# Cube-Panel.net
KiCad netlist of a schematic drawn in EAGLE
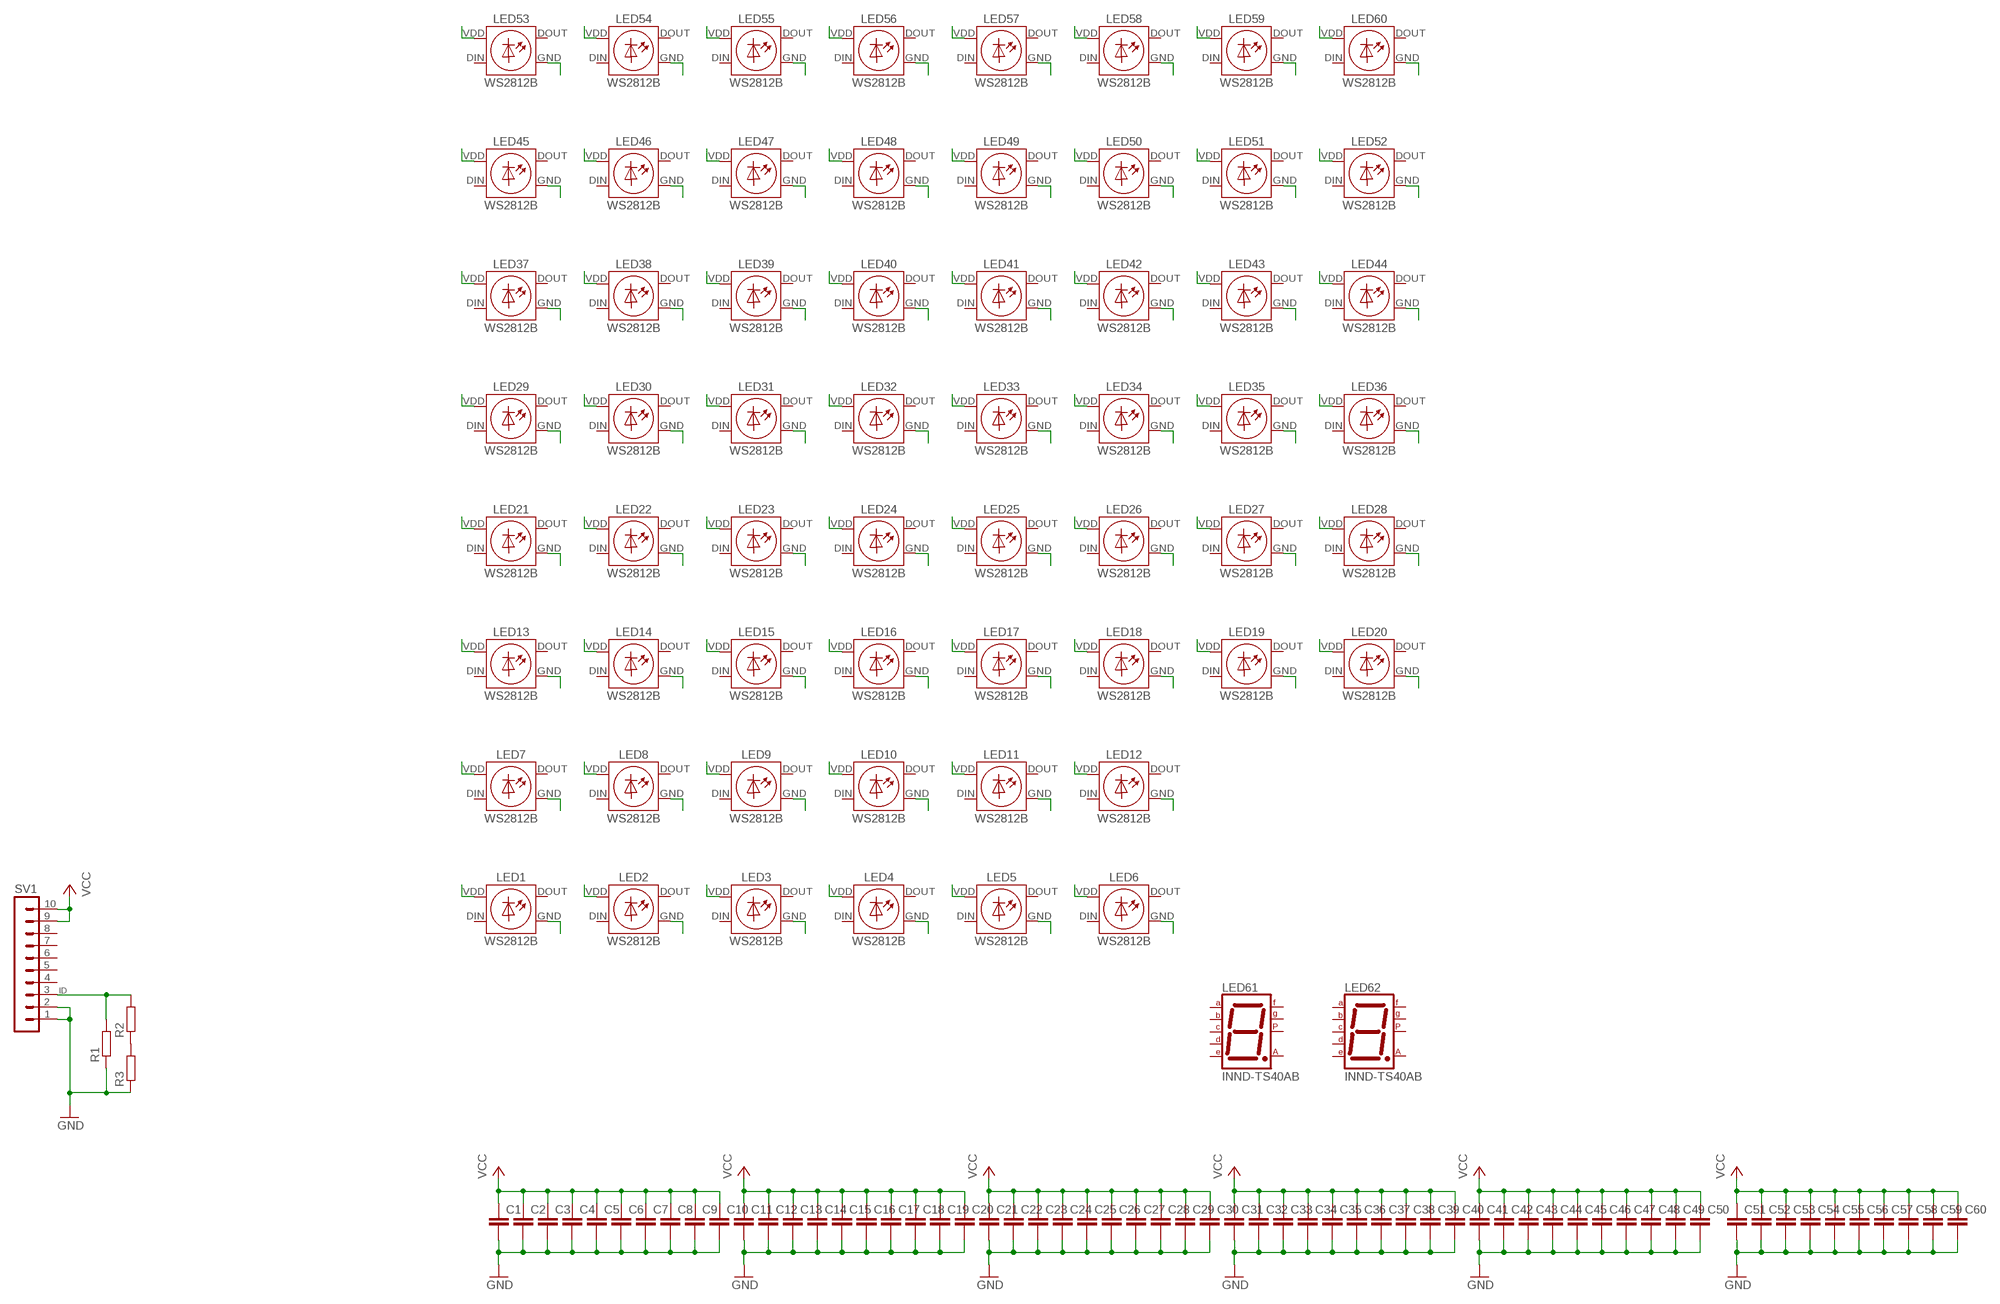
[diagram p0: schematic, sheet 1]

(export (version "E")
  (design (tool "Eeschema 10.0.6"))
  (components
    (comp (ref "C1")
      (value "KONDENSATOR-0603")
      (footprint "eagle-import:0603")
      (libsource (lib "eagle-import") (part "KONDENSATOR-0603"))
    )
    (comp (ref "C2")
      (value "KONDENSATOR-0603")
      (footprint "eagle-import:0603")
      (libsource (lib "eagle-import") (part "KONDENSATOR-0603"))
    )
    (comp (ref "C3")
      (value "KONDENSATOR-0603")
      (footprint "eagle-import:0603")
      (libsource (lib "eagle-import") (part "KONDENSATOR-0603"))
    )
    (comp (ref "C4")
      (value "KONDENSATOR-0603")
      (footprint "eagle-import:0603")
      (libsource (lib "eagle-import") (part "KONDENSATOR-0603"))
    )
    (comp (ref "C5")
      (value "KONDENSATOR-0603")
      (footprint "eagle-import:0603")
      (libsource (lib "eagle-import") (part "KONDENSATOR-0603"))
    )
    (comp (ref "C6")
      (value "KONDENSATOR-0603")
      (footprint "eagle-import:0603")
      (libsource (lib "eagle-import") (part "KONDENSATOR-0603"))
    )
    (comp (ref "C7")
      (value "KONDENSATOR-0603")
      (footprint "eagle-import:0603")
      (libsource (lib "eagle-import") (part "KONDENSATOR-0603"))
    )
    (comp (ref "C8")
      (value "KONDENSATOR-0603")
      (footprint "eagle-import:0603")
      (libsource (lib "eagle-import") (part "KONDENSATOR-0603"))
    )
    (comp (ref "C9")
      (value "KONDENSATOR-0603")
      (footprint "eagle-import:0603")
      (libsource (lib "eagle-import") (part "KONDENSATOR-0603"))
    )
    (comp (ref "C10")
      (value "KONDENSATOR-0603")
      (footprint "eagle-import:0603")
      (libsource (lib "eagle-import") (part "KONDENSATOR-0603"))
    )
    (comp (ref "C11")
      (value "KONDENSATOR-0603")
      (footprint "eagle-import:0603")
      (libsource (lib "eagle-import") (part "KONDENSATOR-0603"))
    )
    (comp (ref "C12")
      (value "KONDENSATOR-0603")
      (footprint "eagle-import:0603")
      (libsource (lib "eagle-import") (part "KONDENSATOR-0603"))
    )
    (comp (ref "C13")
      (value "KONDENSATOR-0603")
      (footprint "eagle-import:0603")
      (libsource (lib "eagle-import") (part "KONDENSATOR-0603"))
    )
    (comp (ref "C14")
      (value "KONDENSATOR-0603")
      (footprint "eagle-import:0603")
      (libsource (lib "eagle-import") (part "KONDENSATOR-0603"))
    )
    (comp (ref "C15")
      (value "KONDENSATOR-0603")
      (footprint "eagle-import:0603")
      (libsource (lib "eagle-import") (part "KONDENSATOR-0603"))
    )
    (comp (ref "C16")
      (value "KONDENSATOR-0603")
      (footprint "eagle-import:0603")
      (libsource (lib "eagle-import") (part "KONDENSATOR-0603"))
    )
    (comp (ref "C17")
      (value "KONDENSATOR-0603")
      (footprint "eagle-import:0603")
      (libsource (lib "eagle-import") (part "KONDENSATOR-0603"))
    )
    (comp (ref "C18")
      (value "KONDENSATOR-0603")
      (footprint "eagle-import:0603")
      (libsource (lib "eagle-import") (part "KONDENSATOR-0603"))
    )
    (comp (ref "C19")
      (value "KONDENSATOR-0603")
      (footprint "eagle-import:0603")
      (libsource (lib "eagle-import") (part "KONDENSATOR-0603"))
    )
    (comp (ref "C20")
      (value "KONDENSATOR-0603")
      (footprint "eagle-import:0603")
      (libsource (lib "eagle-import") (part "KONDENSATOR-0603"))
    )
    (comp (ref "C21")
      (value "KONDENSATOR-0603")
      (footprint "eagle-import:0603")
      (libsource (lib "eagle-import") (part "KONDENSATOR-0603"))
    )
    (comp (ref "C22")
      (value "KONDENSATOR-0603")
      (footprint "eagle-import:0603")
      (libsource (lib "eagle-import") (part "KONDENSATOR-0603"))
    )
    (comp (ref "C23")
      (value "KONDENSATOR-0603")
      (footprint "eagle-import:0603")
      (libsource (lib "eagle-import") (part "KONDENSATOR-0603"))
    )
    (comp (ref "C24")
      (value "KONDENSATOR-0603")
      (footprint "eagle-import:0603")
      (libsource (lib "eagle-import") (part "KONDENSATOR-0603"))
    )
    (comp (ref "C25")
      (value "KONDENSATOR-0603")
      (footprint "eagle-import:0603")
      (libsource (lib "eagle-import") (part "KONDENSATOR-0603"))
    )
    (comp (ref "C26")
      (value "KONDENSATOR-0603")
      (footprint "eagle-import:0603")
      (libsource (lib "eagle-import") (part "KONDENSATOR-0603"))
    )
    (comp (ref "C27")
      (value "KONDENSATOR-0603")
      (footprint "eagle-import:0603")
      (libsource (lib "eagle-import") (part "KONDENSATOR-0603"))
    )
    (comp (ref "C28")
      (value "KONDENSATOR-0603")
      (footprint "eagle-import:0603")
      (libsource (lib "eagle-import") (part "KONDENSATOR-0603"))
    )
    (comp (ref "C29")
      (value "KONDENSATOR-0603")
      (footprint "eagle-import:0603")
      (libsource (lib "eagle-import") (part "KONDENSATOR-0603"))
    )
    (comp (ref "C30")
      (value "KONDENSATOR-0603")
      (footprint "eagle-import:0603")
      (libsource (lib "eagle-import") (part "KONDENSATOR-0603"))
    )
    (comp (ref "C31")
      (value "KONDENSATOR-0603")
      (footprint "eagle-import:0603")
      (libsource (lib "eagle-import") (part "KONDENSATOR-0603"))
    )
    (comp (ref "C32")
      (value "KONDENSATOR-0603")
      (footprint "eagle-import:0603")
      (libsource (lib "eagle-import") (part "KONDENSATOR-0603"))
    )
    (comp (ref "C33")
      (value "KONDENSATOR-0603")
      (footprint "eagle-import:0603")
      (libsource (lib "eagle-import") (part "KONDENSATOR-0603"))
    )
    (comp (ref "C34")
      (value "KONDENSATOR-0603")
      (footprint "eagle-import:0603")
      (libsource (lib "eagle-import") (part "KONDENSATOR-0603"))
    )
    (comp (ref "C35")
      (value "KONDENSATOR-0603")
      (footprint "eagle-import:0603")
      (libsource (lib "eagle-import") (part "KONDENSATOR-0603"))
    )
    (comp (ref "C36")
      (value "KONDENSATOR-0603")
      (footprint "eagle-import:0603")
      (libsource (lib "eagle-import") (part "KONDENSATOR-0603"))
    )
    (comp (ref "C37")
      (value "KONDENSATOR-0603")
      (footprint "eagle-import:0603")
      (libsource (lib "eagle-import") (part "KONDENSATOR-0603"))
    )
    (comp (ref "C38")
      (value "KONDENSATOR-0603")
      (footprint "eagle-import:0603")
      (libsource (lib "eagle-import") (part "KONDENSATOR-0603"))
    )
    (comp (ref "C39")
      (value "KONDENSATOR-0603")
      (footprint "eagle-import:0603")
      (libsource (lib "eagle-import") (part "KONDENSATOR-0603"))
    )
    (comp (ref "C40")
      (value "KONDENSATOR-0603")
      (footprint "eagle-import:0603")
      (libsource (lib "eagle-import") (part "KONDENSATOR-0603"))
    )
    (comp (ref "C41")
      (value "KONDENSATOR-0603")
      (footprint "eagle-import:0603")
      (libsource (lib "eagle-import") (part "KONDENSATOR-0603"))
    )
    (comp (ref "C42")
      (value "KONDENSATOR-0603")
      (footprint "eagle-import:0603")
      (libsource (lib "eagle-import") (part "KONDENSATOR-0603"))
    )
    (comp (ref "C43")
      (value "KONDENSATOR-0603")
      (footprint "eagle-import:0603")
      (libsource (lib "eagle-import") (part "KONDENSATOR-0603"))
    )
    (comp (ref "C44")
      (value "KONDENSATOR-0603")
      (footprint "eagle-import:0603")
      (libsource (lib "eagle-import") (part "KONDENSATOR-0603"))
    )
    (comp (ref "C45")
      (value "KONDENSATOR-0603")
      (footprint "eagle-import:0603")
      (libsource (lib "eagle-import") (part "KONDENSATOR-0603"))
    )
    (comp (ref "C46")
      (value "KONDENSATOR-0603")
      (footprint "eagle-import:0603")
      (libsource (lib "eagle-import") (part "KONDENSATOR-0603"))
    )
    (comp (ref "C47")
      (value "KONDENSATOR-0603")
      (footprint "eagle-import:0603")
      (libsource (lib "eagle-import") (part "KONDENSATOR-0603"))
    )
    (comp (ref "C48")
      (value "KONDENSATOR-0603")
      (footprint "eagle-import:0603")
      (libsource (lib "eagle-import") (part "KONDENSATOR-0603"))
    )
    (comp (ref "C49")
      (value "KONDENSATOR-0603")
      (footprint "eagle-import:0603")
      (libsource (lib "eagle-import") (part "KONDENSATOR-0603"))
    )
    (comp (ref "C50")
      (value "KONDENSATOR-0603")
      (footprint "eagle-import:0603")
      (libsource (lib "eagle-import") (part "KONDENSATOR-0603"))
    )
    (comp (ref "C51")
      (value "KONDENSATOR-0603")
      (footprint "eagle-import:0603")
      (libsource (lib "eagle-import") (part "KONDENSATOR-0603"))
    )
    (comp (ref "C52")
      (value "KONDENSATOR-0603")
      (footprint "eagle-import:0603")
      (libsource (lib "eagle-import") (part "KONDENSATOR-0603"))
    )
    (comp (ref "C53")
      (value "KONDENSATOR-0603")
      (footprint "eagle-import:0603")
      (libsource (lib "eagle-import") (part "KONDENSATOR-0603"))
    )
    (comp (ref "C54")
      (value "KONDENSATOR-0603")
      (footprint "eagle-import:0603")
      (libsource (lib "eagle-import") (part "KONDENSATOR-0603"))
    )
    (comp (ref "C55")
      (value "KONDENSATOR-0603")
      (footprint "eagle-import:0603")
      (libsource (lib "eagle-import") (part "KONDENSATOR-0603"))
    )
    (comp (ref "C56")
      (value "KONDENSATOR-0603")
      (footprint "eagle-import:0603")
      (libsource (lib "eagle-import") (part "KONDENSATOR-0603"))
    )
    (comp (ref "C57")
      (value "KONDENSATOR-0603")
      (footprint "eagle-import:0603")
      (libsource (lib "eagle-import") (part "KONDENSATOR-0603"))
    )
    (comp (ref "C58")
      (value "KONDENSATOR-0603")
      (footprint "eagle-import:0603")
      (libsource (lib "eagle-import") (part "KONDENSATOR-0603"))
    )
    (comp (ref "C59")
      (value "KONDENSATOR-0603")
      (footprint "eagle-import:0603")
      (libsource (lib "eagle-import") (part "KONDENSATOR-0603"))
    )
    (comp (ref "C60")
      (value "KONDENSATOR-0603")
      (footprint "eagle-import:0603")
      (libsource (lib "eagle-import") (part "KONDENSATOR-0603"))
    )
    (comp (ref "LED1")
      (value "WS2812B")
      (footprint "eagle-import:WS2812B")
      (libsource (lib "eagle-import") (part "WS2812B"))
    )
    (comp (ref "LED2")
      (value "WS2812B")
      (footprint "eagle-import:WS2812B")
      (libsource (lib "eagle-import") (part "WS2812B"))
    )
    (comp (ref "LED3")
      (value "WS2812B")
      (footprint "eagle-import:WS2812B")
      (libsource (lib "eagle-import") (part "WS2812B"))
    )
    (comp (ref "LED4")
      (value "WS2812B")
      (footprint "eagle-import:WS2812B")
      (libsource (lib "eagle-import") (part "WS2812B"))
    )
    (comp (ref "LED5")
      (value "WS2812B")
      (footprint "eagle-import:WS2812B")
      (libsource (lib "eagle-import") (part "WS2812B"))
    )
    (comp (ref "LED6")
      (value "WS2812B")
      (footprint "eagle-import:WS2812B")
      (libsource (lib "eagle-import") (part "WS2812B"))
    )
    (comp (ref "LED7")
      (value "WS2812B")
      (footprint "eagle-import:WS2812B")
      (libsource (lib "eagle-import") (part "WS2812B"))
    )
    (comp (ref "LED8")
      (value "WS2812B")
      (footprint "eagle-import:WS2812B")
      (libsource (lib "eagle-import") (part "WS2812B"))
    )
    (comp (ref "LED9")
      (value "WS2812B")
      (footprint "eagle-import:WS2812B")
      (libsource (lib "eagle-import") (part "WS2812B"))
    )
    (comp (ref "LED10")
      (value "WS2812B")
      (footprint "eagle-import:WS2812B")
      (libsource (lib "eagle-import") (part "WS2812B"))
    )
    (comp (ref "LED11")
      (value "WS2812B")
      (footprint "eagle-import:WS2812B")
      (libsource (lib "eagle-import") (part "WS2812B"))
    )
    (comp (ref "LED12")
      (value "WS2812B")
      (footprint "eagle-import:WS2812B")
      (libsource (lib "eagle-import") (part "WS2812B"))
    )
    (comp (ref "LED13")
      (value "WS2812B")
      (footprint "eagle-import:WS2812B")
      (libsource (lib "eagle-import") (part "WS2812B"))
    )
    (comp (ref "LED14")
      (value "WS2812B")
      (footprint "eagle-import:WS2812B")
      (libsource (lib "eagle-import") (part "WS2812B"))
    )
    (comp (ref "LED15")
      (value "WS2812B")
      (footprint "eagle-import:WS2812B")
      (libsource (lib "eagle-import") (part "WS2812B"))
    )
    (comp (ref "LED16")
      (value "WS2812B")
      (footprint "eagle-import:WS2812B")
      (libsource (lib "eagle-import") (part "WS2812B"))
    )
    (comp (ref "LED17")
      (value "WS2812B")
      (footprint "eagle-import:WS2812B")
      (libsource (lib "eagle-import") (part "WS2812B"))
    )
    (comp (ref "LED18")
      (value "WS2812B")
      (footprint "eagle-import:WS2812B")
      (libsource (lib "eagle-import") (part "WS2812B"))
    )
    (comp (ref "LED19")
      (value "WS2812B")
      (footprint "eagle-import:WS2812B")
      (libsource (lib "eagle-import") (part "WS2812B"))
    )
    (comp (ref "LED20")
      (value "WS2812B")
      (footprint "eagle-import:WS2812B")
      (libsource (lib "eagle-import") (part "WS2812B"))
    )
    (comp (ref "LED21")
      (value "WS2812B")
      (footprint "eagle-import:WS2812B")
      (libsource (lib "eagle-import") (part "WS2812B"))
    )
    (comp (ref "LED22")
      (value "WS2812B")
      (footprint "eagle-import:WS2812B")
      (libsource (lib "eagle-import") (part "WS2812B"))
    )
    (comp (ref "LED23")
      (value "WS2812B")
      (footprint "eagle-import:WS2812B")
      (libsource (lib "eagle-import") (part "WS2812B"))
    )
    (comp (ref "LED24")
      (value "WS2812B")
      (footprint "eagle-import:WS2812B")
      (libsource (lib "eagle-import") (part "WS2812B"))
    )
    (comp (ref "LED25")
      (value "WS2812B")
      (footprint "eagle-import:WS2812B")
      (libsource (lib "eagle-import") (part "WS2812B"))
    )
    (comp (ref "LED26")
      (value "WS2812B")
      (footprint "eagle-import:WS2812B")
      (libsource (lib "eagle-import") (part "WS2812B"))
    )
    (comp (ref "LED27")
      (value "WS2812B")
      (footprint "eagle-import:WS2812B")
      (libsource (lib "eagle-import") (part "WS2812B"))
    )
    (comp (ref "LED28")
      (value "WS2812B")
      (footprint "eagle-import:WS2812B")
      (libsource (lib "eagle-import") (part "WS2812B"))
    )
    (comp (ref "LED29")
      (value "WS2812B")
      (footprint "eagle-import:WS2812B")
      (libsource (lib "eagle-import") (part "WS2812B"))
    )
    (comp (ref "LED30")
      (value "WS2812B")
      (footprint "eagle-import:WS2812B")
      (libsource (lib "eagle-import") (part "WS2812B"))
    )
    (comp (ref "LED31")
      (value "WS2812B")
      (footprint "eagle-import:WS2812B")
      (libsource (lib "eagle-import") (part "WS2812B"))
    )
    (comp (ref "LED32")
      (value "WS2812B")
      (footprint "eagle-import:WS2812B")
      (libsource (lib "eagle-import") (part "WS2812B"))
    )
    (comp (ref "LED33")
      (value "WS2812B")
      (footprint "eagle-import:WS2812B")
      (libsource (lib "eagle-import") (part "WS2812B"))
    )
    (comp (ref "LED34")
      (value "WS2812B")
      (footprint "eagle-import:WS2812B")
      (libsource (lib "eagle-import") (part "WS2812B"))
    )
    (comp (ref "LED35")
      (value "WS2812B")
      (footprint "eagle-import:WS2812B")
      (libsource (lib "eagle-import") (part "WS2812B"))
    )
    (comp (ref "LED36")
      (value "WS2812B")
      (footprint "eagle-import:WS2812B")
      (libsource (lib "eagle-import") (part "WS2812B"))
    )
    (comp (ref "LED37")
      (value "WS2812B")
      (footprint "eagle-import:WS2812B")
      (libsource (lib "eagle-import") (part "WS2812B"))
    )
    (comp (ref "LED38")
      (value "WS2812B")
      (footprint "eagle-import:WS2812B")
      (libsource (lib "eagle-import") (part "WS2812B"))
    )
    (comp (ref "LED39")
      (value "WS2812B")
      (footprint "eagle-import:WS2812B")
      (libsource (lib "eagle-import") (part "WS2812B"))
    )
    (comp (ref "LED40")
      (value "WS2812B")
      (footprint "eagle-import:WS2812B")
      (libsource (lib "eagle-import") (part "WS2812B"))
    )
    (comp (ref "LED41")
      (value "WS2812B")
      (footprint "eagle-import:WS2812B")
      (libsource (lib "eagle-import") (part "WS2812B"))
    )
    (comp (ref "LED42")
      (value "WS2812B")
      (footprint "eagle-import:WS2812B")
      (libsource (lib "eagle-import") (part "WS2812B"))
    )
    (comp (ref "LED43")
      (value "WS2812B")
      (footprint "eagle-import:WS2812B")
      (libsource (lib "eagle-import") (part "WS2812B"))
    )
    (comp (ref "LED44")
      (value "WS2812B")
      (footprint "eagle-import:WS2812B")
      (libsource (lib "eagle-import") (part "WS2812B"))
    )
    (comp (ref "LED45")
      (value "WS2812B")
      (footprint "eagle-import:WS2812B")
      (libsource (lib "eagle-import") (part "WS2812B"))
    )
    (comp (ref "LED46")
      (value "WS2812B")
      (footprint "eagle-import:WS2812B")
      (libsource (lib "eagle-import") (part "WS2812B"))
    )
    (comp (ref "LED47")
      (value "WS2812B")
      (footprint "eagle-import:WS2812B")
      (libsource (lib "eagle-import") (part "WS2812B"))
    )
    (comp (ref "LED48")
      (value "WS2812B")
      (footprint "eagle-import:WS2812B")
      (libsource (lib "eagle-import") (part "WS2812B"))
    )
    (comp (ref "LED49")
      (value "WS2812B")
      (footprint "eagle-import:WS2812B")
      (libsource (lib "eagle-import") (part "WS2812B"))
    )
    (comp (ref "LED50")
      (value "WS2812B")
      (footprint "eagle-import:WS2812B")
      (libsource (lib "eagle-import") (part "WS2812B"))
    )
    (comp (ref "LED51")
      (value "WS2812B")
      (footprint "eagle-import:WS2812B")
      (libsource (lib "eagle-import") (part "WS2812B"))
    )
    (comp (ref "LED52")
      (value "WS2812B")
      (footprint "eagle-import:WS2812B")
      (libsource (lib "eagle-import") (part "WS2812B"))
    )
    (comp (ref "LED53")
      (value "WS2812B")
      (footprint "eagle-import:WS2812B")
      (libsource (lib "eagle-import") (part "WS2812B"))
    )
    (comp (ref "LED54")
      (value "WS2812B")
      (footprint "eagle-import:WS2812B")
      (libsource (lib "eagle-import") (part "WS2812B"))
    )
    (comp (ref "LED55")
      (value "WS2812B")
      (footprint "eagle-import:WS2812B")
      (libsource (lib "eagle-import") (part "WS2812B"))
    )
    (comp (ref "LED56")
      (value "WS2812B")
      (footprint "eagle-import:WS2812B")
      (libsource (lib "eagle-import") (part "WS2812B"))
    )
    (comp (ref "LED57")
      (value "WS2812B")
      (footprint "eagle-import:WS2812B")
      (libsource (lib "eagle-import") (part "WS2812B"))
    )
    (comp (ref "LED58")
      (value "WS2812B")
      (footprint "eagle-import:WS2812B")
      (libsource (lib "eagle-import") (part "WS2812B"))
    )
    (comp (ref "LED59")
      (value "WS2812B")
      (footprint "eagle-import:WS2812B")
      (libsource (lib "eagle-import") (part "WS2812B"))
    )
    (comp (ref "LED60")
      (value "WS2812B")
      (footprint "eagle-import:WS2812B")
      (libsource (lib "eagle-import") (part "WS2812B"))
    )
    (comp (ref "LED61")
      (value "INND-TS40AB")
      (footprint "eagle-import:7SEG-13")
      (libsource (lib "eagle-import") (part "INND-TS40AB"))
    )
    (comp (ref "LED62")
      (value "INND-TS40AB")
      (footprint "eagle-import:7SEG-13")
      (libsource (lib "eagle-import") (part "INND-TS40AB"))
    )
    (comp (ref "R1")
      (value "WIDERSTAND_0603")
      (footprint "eagle-import:R0603")
      (libsource (lib "eagle-import") (part "WIDERSTAND_0603"))
    )
    (comp (ref "R2")
      (value "WIDERSTAND_0603")
      (footprint "eagle-import:R0603")
      (libsource (lib "eagle-import") (part "WIDERSTAND_0603"))
    )
    (comp (ref "R3")
      (value "WIDERSTAND_0603")
      (footprint "eagle-import:R0603")
      (libsource (lib "eagle-import") (part "WIDERSTAND_0603"))
    )
    (comp (ref "SV1")
      (value "MA10-1")
      (footprint "eagle-import:MA10-1")
      (libsource (lib "eagle-import") (part "MA10-1"))
    )
  )
  (nets
    (net (code "1") (name "/ID") (class "Default")
      (node (ref "R1") (pin "2") (pinfunction "2_2") (pintype "passive"))
      (node (ref "R2") (pin "2") (pinfunction "2_2") (pintype "passive"))
      (node (ref "SV1") (pin "3") (pinfunction "3_3") (pintype "passive"))
    )
    (net (code "2") (name "GND") (class "Default")
      (node (ref "C1") (pin "P$2") (pinfunction "2_P$2") (pintype "passive"))
      (node (ref "C10") (pin "P$2") (pinfunction "2_P$2") (pintype "passive"))
      (node (ref "C11") (pin "P$2") (pinfunction "2_P$2") (pintype "passive"))
      (node (ref "C12") (pin "P$2") (pinfunction "2_P$2") (pintype "passive"))
      (node (ref "C13") (pin "P$2") (pinfunction "2_P$2") (pintype "passive"))
      (node (ref "C14") (pin "P$2") (pinfunction "2_P$2") (pintype "passive"))
      (node (ref "C15") (pin "P$2") (pinfunction "2_P$2") (pintype "passive"))
      (node (ref "C16") (pin "P$2") (pinfunction "2_P$2") (pintype "passive"))
      (node (ref "C17") (pin "P$2") (pinfunction "2_P$2") (pintype "passive"))
      (node (ref "C18") (pin "P$2") (pinfunction "2_P$2") (pintype "passive"))
      (node (ref "C19") (pin "P$2") (pinfunction "2_P$2") (pintype "passive"))
      (node (ref "C2") (pin "P$2") (pinfunction "2_P$2") (pintype "passive"))
      (node (ref "C20") (pin "P$2") (pinfunction "2_P$2") (pintype "passive"))
      (node (ref "C21") (pin "P$2") (pinfunction "2_P$2") (pintype "passive"))
      (node (ref "C22") (pin "P$2") (pinfunction "2_P$2") (pintype "passive"))
      (node (ref "C23") (pin "P$2") (pinfunction "2_P$2") (pintype "passive"))
      (node (ref "C24") (pin "P$2") (pinfunction "2_P$2") (pintype "passive"))
      (node (ref "C25") (pin "P$2") (pinfunction "2_P$2") (pintype "passive"))
      (node (ref "C26") (pin "P$2") (pinfunction "2_P$2") (pintype "passive"))
      (node (ref "C27") (pin "P$2") (pinfunction "2_P$2") (pintype "passive"))
      (node (ref "C28") (pin "P$2") (pinfunction "2_P$2") (pintype "passive"))
      (node (ref "C29") (pin "P$2") (pinfunction "2_P$2") (pintype "passive"))
      (node (ref "C3") (pin "P$2") (pinfunction "2_P$2") (pintype "passive"))
      (node (ref "C30") (pin "P$2") (pinfunction "2_P$2") (pintype "passive"))
      (node (ref "C31") (pin "P$2") (pinfunction "2_P$2") (pintype "passive"))
      (node (ref "C32") (pin "P$2") (pinfunction "2_P$2") (pintype "passive"))
      (node (ref "C33") (pin "P$2") (pinfunction "2_P$2") (pintype "passive"))
      (node (ref "C34") (pin "P$2") (pinfunction "2_P$2") (pintype "passive"))
      (node (ref "C35") (pin "P$2") (pinfunction "2_P$2") (pintype "passive"))
      (node (ref "C36") (pin "P$2") (pinfunction "2_P$2") (pintype "passive"))
      (node (ref "C37") (pin "P$2") (pinfunction "2_P$2") (pintype "passive"))
      (node (ref "C38") (pin "P$2") (pinfunction "2_P$2") (pintype "passive"))
      (node (ref "C39") (pin "P$2") (pinfunction "2_P$2") (pintype "passive"))
      (node (ref "C4") (pin "P$2") (pinfunction "2_P$2") (pintype "passive"))
      (node (ref "C40") (pin "P$2") (pinfunction "2_P$2") (pintype "passive"))
      (node (ref "C41") (pin "P$2") (pinfunction "2_P$2") (pintype "passive"))
      (node (ref "C42") (pin "P$2") (pinfunction "2_P$2") (pintype "passive"))
      (node (ref "C43") (pin "P$2") (pinfunction "2_P$2") (pintype "passive"))
      (node (ref "C44") (pin "P$2") (pinfunction "2_P$2") (pintype "passive"))
      (node (ref "C45") (pin "P$2") (pinfunction "2_P$2") (pintype "passive"))
      (node (ref "C46") (pin "P$2") (pinfunction "2_P$2") (pintype "passive"))
      (node (ref "C47") (pin "P$2") (pinfunction "2_P$2") (pintype "passive"))
      (node (ref "C48") (pin "P$2") (pinfunction "2_P$2") (pintype "passive"))
      (node (ref "C49") (pin "P$2") (pinfunction "2_P$2") (pintype "passive"))
      (node (ref "C5") (pin "P$2") (pinfunction "2_P$2") (pintype "passive"))
      (node (ref "C50") (pin "P$2") (pinfunction "2_P$2") (pintype "passive"))
      (node (ref "C51") (pin "P$2") (pinfunction "2_P$2") (pintype "passive"))
      (node (ref "C52") (pin "P$2") (pinfunction "2_P$2") (pintype "passive"))
      (node (ref "C53") (pin "P$2") (pinfunction "2_P$2") (pintype "passive"))
      (node (ref "C54") (pin "P$2") (pinfunction "2_P$2") (pintype "passive"))
      (node (ref "C55") (pin "P$2") (pinfunction "2_P$2") (pintype "passive"))
      (node (ref "C56") (pin "P$2") (pinfunction "2_P$2") (pintype "passive"))
      (node (ref "C57") (pin "P$2") (pinfunction "2_P$2") (pintype "passive"))
      (node (ref "C58") (pin "P$2") (pinfunction "2_P$2") (pintype "passive"))
      (node (ref "C59") (pin "P$2") (pinfunction "2_P$2") (pintype "passive"))
      (node (ref "C6") (pin "P$2") (pinfunction "2_P$2") (pintype "passive"))
      (node (ref "C60") (pin "P$2") (pinfunction "2_P$2") (pintype "passive"))
      (node (ref "C7") (pin "P$2") (pinfunction "2_P$2") (pintype "passive"))
      (node (ref "C8") (pin "P$2") (pinfunction "2_P$2") (pintype "passive"))
      (node (ref "C9") (pin "P$2") (pinfunction "2_P$2") (pintype "passive"))
      (node (ref "LED1") (pin "GND") (pinfunction "GND_GND") (pintype "power_in"))
      (node (ref "LED10") (pin "GND") (pinfunction "GND_GND") (pintype "power_in"))
      (node (ref "LED11") (pin "GND") (pinfunction "GND_GND") (pintype "power_in"))
      (node (ref "LED12") (pin "GND") (pinfunction "GND_GND") (pintype "power_in"))
      (node (ref "LED13") (pin "GND") (pinfunction "GND_GND") (pintype "power_in"))
      (node (ref "LED14") (pin "GND") (pinfunction "GND_GND") (pintype "power_in"))
      (node (ref "LED15") (pin "GND") (pinfunction "GND_GND") (pintype "power_in"))
      (node (ref "LED16") (pin "GND") (pinfunction "GND_GND") (pintype "power_in"))
      (node (ref "LED17") (pin "GND") (pinfunction "GND_GND") (pintype "power_in"))
      (node (ref "LED18") (pin "GND") (pinfunction "GND_GND") (pintype "power_in"))
      (node (ref "LED19") (pin "GND") (pinfunction "GND_GND") (pintype "power_in"))
      (node (ref "LED2") (pin "GND") (pinfunction "GND_GND") (pintype "power_in"))
      (node (ref "LED20") (pin "GND") (pinfunction "GND_GND") (pintype "power_in"))
      (node (ref "LED21") (pin "GND") (pinfunction "GND_GND") (pintype "power_in"))
      (node (ref "LED22") (pin "GND") (pinfunction "GND_GND") (pintype "power_in"))
      (node (ref "LED23") (pin "GND") (pinfunction "GND_GND") (pintype "power_in"))
      (node (ref "LED24") (pin "GND") (pinfunction "GND_GND") (pintype "power_in"))
      (node (ref "LED25") (pin "GND") (pinfunction "GND_GND") (pintype "power_in"))
      (node (ref "LED26") (pin "GND") (pinfunction "GND_GND") (pintype "power_in"))
      (node (ref "LED27") (pin "GND") (pinfunction "GND_GND") (pintype "power_in"))
      (node (ref "LED28") (pin "GND") (pinfunction "GND_GND") (pintype "power_in"))
      (node (ref "LED29") (pin "GND") (pinfunction "GND_GND") (pintype "power_in"))
      (node (ref "LED3") (pin "GND") (pinfunction "GND_GND") (pintype "power_in"))
      (node (ref "LED30") (pin "GND") (pinfunction "GND_GND") (pintype "power_in"))
      (node (ref "LED31") (pin "GND") (pinfunction "GND_GND") (pintype "power_in"))
      (node (ref "LED32") (pin "GND") (pinfunction "GND_GND") (pintype "power_in"))
      (node (ref "LED33") (pin "GND") (pinfunction "GND_GND") (pintype "power_in"))
      (node (ref "LED34") (pin "GND") (pinfunction "GND_GND") (pintype "power_in"))
      (node (ref "LED35") (pin "GND") (pinfunction "GND_GND") (pintype "power_in"))
      (node (ref "LED36") (pin "GND") (pinfunction "GND_GND") (pintype "power_in"))
      (node (ref "LED37") (pin "GND") (pinfunction "GND_GND") (pintype "power_in"))
      (node (ref "LED38") (pin "GND") (pinfunction "GND_GND") (pintype "power_in"))
      (node (ref "LED39") (pin "GND") (pinfunction "GND_GND") (pintype "power_in"))
      (node (ref "LED4") (pin "GND") (pinfunction "GND_GND") (pintype "power_in"))
      (node (ref "LED40") (pin "GND") (pinfunction "GND_GND") (pintype "power_in"))
      (node (ref "LED41") (pin "GND") (pinfunction "GND_GND") (pintype "power_in"))
      (node (ref "LED42") (pin "GND") (pinfunction "GND_GND") (pintype "power_in"))
      (node (ref "LED43") (pin "GND") (pinfunction "GND_GND") (pintype "power_in"))
      (node (ref "LED44") (pin "GND") (pinfunction "GND_GND") (pintype "power_in"))
      (node (ref "LED45") (pin "GND") (pinfunction "GND_GND") (pintype "power_in"))
      (node (ref "LED46") (pin "GND") (pinfunction "GND_GND") (pintype "power_in"))
      (node (ref "LED47") (pin "GND") (pinfunction "GND_GND") (pintype "power_in"))
      (node (ref "LED48") (pin "GND") (pinfunction "GND_GND") (pintype "power_in"))
      (node (ref "LED49") (pin "GND") (pinfunction "GND_GND") (pintype "power_in"))
      (node (ref "LED5") (pin "GND") (pinfunction "GND_GND") (pintype "power_in"))
      (node (ref "LED50") (pin "GND") (pinfunction "GND_GND") (pintype "power_in"))
      (node (ref "LED51") (pin "GND") (pinfunction "GND_GND") (pintype "power_in"))
      (node (ref "LED52") (pin "GND") (pinfunction "GND_GND") (pintype "power_in"))
      (node (ref "LED53") (pin "GND") (pinfunction "GND_GND") (pintype "power_in"))
      (node (ref "LED54") (pin "GND") (pinfunction "GND_GND") (pintype "power_in"))
      (node (ref "LED55") (pin "GND") (pinfunction "GND_GND") (pintype "power_in"))
      (node (ref "LED56") (pin "GND") (pinfunction "GND_GND") (pintype "power_in"))
      (node (ref "LED57") (pin "GND") (pinfunction "GND_GND") (pintype "power_in"))
      (node (ref "LED58") (pin "GND") (pinfunction "GND_GND") (pintype "power_in"))
      (node (ref "LED59") (pin "GND") (pinfunction "GND_GND") (pintype "power_in"))
      (node (ref "LED6") (pin "GND") (pinfunction "GND_GND") (pintype "power_in"))
      (node (ref "LED60") (pin "GND") (pinfunction "GND_GND") (pintype "power_in"))
      (node (ref "LED7") (pin "GND") (pinfunction "GND_GND") (pintype "power_in"))
      (node (ref "LED8") (pin "GND") (pinfunction "GND_GND") (pintype "power_in"))
      (node (ref "LED9") (pin "GND") (pinfunction "GND_GND") (pintype "power_in"))
      (node (ref "R1") (pin "1") (pinfunction "1_1") (pintype "passive"))
      (node (ref "R3") (pin "1") (pinfunction "1_1") (pintype "passive"))
      (node (ref "SV1") (pin "1") (pinfunction "1_1") (pintype "passive"))
      (node (ref "SV1") (pin "2") (pinfunction "2_2") (pintype "passive"))
    )
    (net (code "3") (name "Net-(R2-Pad1)") (class "Default")
      (node (ref "R2") (pin "1") (pinfunction "1_1") (pintype "passive"))
      (node (ref "R3") (pin "2") (pinfunction "2_2") (pintype "passive"))
    )
    (net (code "4") (name "VCC") (class "Default")
      (node (ref "C1") (pin "P$1") (pinfunction "1_P$1") (pintype "passive"))
      (node (ref "C10") (pin "P$1") (pinfunction "1_P$1") (pintype "passive"))
      (node (ref "C11") (pin "P$1") (pinfunction "1_P$1") (pintype "passive"))
      (node (ref "C12") (pin "P$1") (pinfunction "1_P$1") (pintype "passive"))
      (node (ref "C13") (pin "P$1") (pinfunction "1_P$1") (pintype "passive"))
      (node (ref "C14") (pin "P$1") (pinfunction "1_P$1") (pintype "passive"))
      (node (ref "C15") (pin "P$1") (pinfunction "1_P$1") (pintype "passive"))
      (node (ref "C16") (pin "P$1") (pinfunction "1_P$1") (pintype "passive"))
      (node (ref "C17") (pin "P$1") (pinfunction "1_P$1") (pintype "passive"))
      (node (ref "C18") (pin "P$1") (pinfunction "1_P$1") (pintype "passive"))
      (node (ref "C19") (pin "P$1") (pinfunction "1_P$1") (pintype "passive"))
      (node (ref "C2") (pin "P$1") (pinfunction "1_P$1") (pintype "passive"))
      (node (ref "C20") (pin "P$1") (pinfunction "1_P$1") (pintype "passive"))
      (node (ref "C21") (pin "P$1") (pinfunction "1_P$1") (pintype "passive"))
      (node (ref "C22") (pin "P$1") (pinfunction "1_P$1") (pintype "passive"))
      (node (ref "C23") (pin "P$1") (pinfunction "1_P$1") (pintype "passive"))
      (node (ref "C24") (pin "P$1") (pinfunction "1_P$1") (pintype "passive"))
      (node (ref "C25") (pin "P$1") (pinfunction "1_P$1") (pintype "passive"))
      (node (ref "C26") (pin "P$1") (pinfunction "1_P$1") (pintype "passive"))
      (node (ref "C27") (pin "P$1") (pinfunction "1_P$1") (pintype "passive"))
      (node (ref "C28") (pin "P$1") (pinfunction "1_P$1") (pintype "passive"))
      (node (ref "C29") (pin "P$1") (pinfunction "1_P$1") (pintype "passive"))
      (node (ref "C3") (pin "P$1") (pinfunction "1_P$1") (pintype "passive"))
      (node (ref "C30") (pin "P$1") (pinfunction "1_P$1") (pintype "passive"))
      (node (ref "C31") (pin "P$1") (pinfunction "1_P$1") (pintype "passive"))
      (node (ref "C32") (pin "P$1") (pinfunction "1_P$1") (pintype "passive"))
      (node (ref "C33") (pin "P$1") (pinfunction "1_P$1") (pintype "passive"))
      (node (ref "C34") (pin "P$1") (pinfunction "1_P$1") (pintype "passive"))
      (node (ref "C35") (pin "P$1") (pinfunction "1_P$1") (pintype "passive"))
      (node (ref "C36") (pin "P$1") (pinfunction "1_P$1") (pintype "passive"))
      (node (ref "C37") (pin "P$1") (pinfunction "1_P$1") (pintype "passive"))
      (node (ref "C38") (pin "P$1") (pinfunction "1_P$1") (pintype "passive"))
      (node (ref "C39") (pin "P$1") (pinfunction "1_P$1") (pintype "passive"))
      (node (ref "C4") (pin "P$1") (pinfunction "1_P$1") (pintype "passive"))
      (node (ref "C40") (pin "P$1") (pinfunction "1_P$1") (pintype "passive"))
      (node (ref "C41") (pin "P$1") (pinfunction "1_P$1") (pintype "passive"))
      (node (ref "C42") (pin "P$1") (pinfunction "1_P$1") (pintype "passive"))
      (node (ref "C43") (pin "P$1") (pinfunction "1_P$1") (pintype "passive"))
      (node (ref "C44") (pin "P$1") (pinfunction "1_P$1") (pintype "passive"))
      (node (ref "C45") (pin "P$1") (pinfunction "1_P$1") (pintype "passive"))
      (node (ref "C46") (pin "P$1") (pinfunction "1_P$1") (pintype "passive"))
      (node (ref "C47") (pin "P$1") (pinfunction "1_P$1") (pintype "passive"))
      (node (ref "C48") (pin "P$1") (pinfunction "1_P$1") (pintype "passive"))
      (node (ref "C49") (pin "P$1") (pinfunction "1_P$1") (pintype "passive"))
      (node (ref "C5") (pin "P$1") (pinfunction "1_P$1") (pintype "passive"))
      (node (ref "C50") (pin "P$1") (pinfunction "1_P$1") (pintype "passive"))
      (node (ref "C51") (pin "P$1") (pinfunction "1_P$1") (pintype "passive"))
      (node (ref "C52") (pin "P$1") (pinfunction "1_P$1") (pintype "passive"))
      (node (ref "C53") (pin "P$1") (pinfunction "1_P$1") (pintype "passive"))
      (node (ref "C54") (pin "P$1") (pinfunction "1_P$1") (pintype "passive"))
      (node (ref "C55") (pin "P$1") (pinfunction "1_P$1") (pintype "passive"))
      (node (ref "C56") (pin "P$1") (pinfunction "1_P$1") (pintype "passive"))
      (node (ref "C57") (pin "P$1") (pinfunction "1_P$1") (pintype "passive"))
      (node (ref "C58") (pin "P$1") (pinfunction "1_P$1") (pintype "passive"))
      (node (ref "C59") (pin "P$1") (pinfunction "1_P$1") (pintype "passive"))
      (node (ref "C6") (pin "P$1") (pinfunction "1_P$1") (pintype "passive"))
      (node (ref "C60") (pin "P$1") (pinfunction "1_P$1") (pintype "passive"))
      (node (ref "C7") (pin "P$1") (pinfunction "1_P$1") (pintype "passive"))
      (node (ref "C8") (pin "P$1") (pinfunction "1_P$1") (pintype "passive"))
      (node (ref "C9") (pin "P$1") (pinfunction "1_P$1") (pintype "passive"))
      (node (ref "LED1") (pin "VDD") (pinfunction "VCC_VDD") (pintype "power_in"))
      (node (ref "LED10") (pin "VDD") (pinfunction "VCC_VDD") (pintype "power_in"))
      (node (ref "LED11") (pin "VDD") (pinfunction "VCC_VDD") (pintype "power_in"))
      (node (ref "LED12") (pin "VDD") (pinfunction "VCC_VDD") (pintype "power_in"))
      (node (ref "LED13") (pin "VDD") (pinfunction "VCC_VDD") (pintype "power_in"))
      (node (ref "LED14") (pin "VDD") (pinfunction "VCC_VDD") (pintype "power_in"))
      (node (ref "LED15") (pin "VDD") (pinfunction "VCC_VDD") (pintype "power_in"))
      (node (ref "LED16") (pin "VDD") (pinfunction "VCC_VDD") (pintype "power_in"))
      (node (ref "LED17") (pin "VDD") (pinfunction "VCC_VDD") (pintype "power_in"))
      (node (ref "LED18") (pin "VDD") (pinfunction "VCC_VDD") (pintype "power_in"))
      (node (ref "LED19") (pin "VDD") (pinfunction "VCC_VDD") (pintype "power_in"))
      (node (ref "LED2") (pin "VDD") (pinfunction "VCC_VDD") (pintype "power_in"))
      (node (ref "LED20") (pin "VDD") (pinfunction "VCC_VDD") (pintype "power_in"))
      (node (ref "LED21") (pin "VDD") (pinfunction "VCC_VDD") (pintype "power_in"))
      (node (ref "LED22") (pin "VDD") (pinfunction "VCC_VDD") (pintype "power_in"))
      (node (ref "LED23") (pin "VDD") (pinfunction "VCC_VDD") (pintype "power_in"))
      (node (ref "LED24") (pin "VDD") (pinfunction "VCC_VDD") (pintype "power_in"))
      (node (ref "LED25") (pin "VDD") (pinfunction "VCC_VDD") (pintype "power_in"))
      (node (ref "LED26") (pin "VDD") (pinfunction "VCC_VDD") (pintype "power_in"))
      (node (ref "LED27") (pin "VDD") (pinfunction "VCC_VDD") (pintype "power_in"))
      (node (ref "LED28") (pin "VDD") (pinfunction "VCC_VDD") (pintype "power_in"))
      (node (ref "LED29") (pin "VDD") (pinfunction "VCC_VDD") (pintype "power_in"))
      (node (ref "LED3") (pin "VDD") (pinfunction "VCC_VDD") (pintype "power_in"))
      (node (ref "LED30") (pin "VDD") (pinfunction "VCC_VDD") (pintype "power_in"))
      (node (ref "LED31") (pin "VDD") (pinfunction "VCC_VDD") (pintype "power_in"))
      (node (ref "LED32") (pin "VDD") (pinfunction "VCC_VDD") (pintype "power_in"))
      (node (ref "LED33") (pin "VDD") (pinfunction "VCC_VDD") (pintype "power_in"))
      (node (ref "LED34") (pin "VDD") (pinfunction "VCC_VDD") (pintype "power_in"))
      (node (ref "LED35") (pin "VDD") (pinfunction "VCC_VDD") (pintype "power_in"))
      (node (ref "LED36") (pin "VDD") (pinfunction "VCC_VDD") (pintype "power_in"))
      (node (ref "LED37") (pin "VDD") (pinfunction "VCC_VDD") (pintype "power_in"))
      (node (ref "LED38") (pin "VDD") (pinfunction "VCC_VDD") (pintype "power_in"))
      (node (ref "LED39") (pin "VDD") (pinfunction "VCC_VDD") (pintype "power_in"))
      (node (ref "LED4") (pin "VDD") (pinfunction "VCC_VDD") (pintype "power_in"))
      (node (ref "LED40") (pin "VDD") (pinfunction "VCC_VDD") (pintype "power_in"))
      (node (ref "LED41") (pin "VDD") (pinfunction "VCC_VDD") (pintype "power_in"))
      (node (ref "LED42") (pin "VDD") (pinfunction "VCC_VDD") (pintype "power_in"))
      (node (ref "LED43") (pin "VDD") (pinfunction "VCC_VDD") (pintype "power_in"))
      (node (ref "LED44") (pin "VDD") (pinfunction "VCC_VDD") (pintype "power_in"))
      (node (ref "LED45") (pin "VDD") (pinfunction "VCC_VDD") (pintype "power_in"))
      (node (ref "LED46") (pin "VDD") (pinfunction "VCC_VDD") (pintype "power_in"))
      (node (ref "LED47") (pin "VDD") (pinfunction "VCC_VDD") (pintype "power_in"))
      (node (ref "LED48") (pin "VDD") (pinfunction "VCC_VDD") (pintype "power_in"))
      (node (ref "LED49") (pin "VDD") (pinfunction "VCC_VDD") (pintype "power_in"))
      (node (ref "LED5") (pin "VDD") (pinfunction "VCC_VDD") (pintype "power_in"))
      (node (ref "LED50") (pin "VDD") (pinfunction "VCC_VDD") (pintype "power_in"))
      (node (ref "LED51") (pin "VDD") (pinfunction "VCC_VDD") (pintype "power_in"))
      (node (ref "LED52") (pin "VDD") (pinfunction "VCC_VDD") (pintype "power_in"))
      (node (ref "LED53") (pin "VDD") (pinfunction "VCC_VDD") (pintype "power_in"))
      (node (ref "LED54") (pin "VDD") (pinfunction "VCC_VDD") (pintype "power_in"))
      (node (ref "LED55") (pin "VDD") (pinfunction "VCC_VDD") (pintype "power_in"))
      (node (ref "LED56") (pin "VDD") (pinfunction "VCC_VDD") (pintype "power_in"))
      (node (ref "LED57") (pin "VDD") (pinfunction "VCC_VDD") (pintype "power_in"))
      (node (ref "LED58") (pin "VDD") (pinfunction "VCC_VDD") (pintype "power_in"))
      (node (ref "LED59") (pin "VDD") (pinfunction "VCC_VDD") (pintype "power_in"))
      (node (ref "LED6") (pin "VDD") (pinfunction "VCC_VDD") (pintype "power_in"))
      (node (ref "LED60") (pin "VDD") (pinfunction "VCC_VDD") (pintype "power_in"))
      (node (ref "LED7") (pin "VDD") (pinfunction "VCC_VDD") (pintype "power_in"))
      (node (ref "LED8") (pin "VDD") (pinfunction "VCC_VDD") (pintype "power_in"))
      (node (ref "LED9") (pin "VDD") (pinfunction "VCC_VDD") (pintype "power_in"))
      (node (ref "SV1") (pin "10") (pinfunction "10_10") (pintype "passive"))
      (node (ref "SV1") (pin "9") (pinfunction "9_9") (pintype "passive"))
    )
    (net (code "5") (name "unconnected-(LED1-PadDIN)") (class "Default")
      (node (ref "LED1") (pin "DIN") (pinfunction "DIN_DIN") (pintype "input"))
    )
    (net (code "6") (name "unconnected-(LED1-PadDOUT)") (class "Default")
      (node (ref "LED1") (pin "DOUT") (pinfunction "DOUT_DOUT") (pintype "output"))
    )
    (net (code "7") (name "unconnected-(LED2-PadDIN)") (class "Default")
      (node (ref "LED2") (pin "DIN") (pinfunction "DIN_DIN") (pintype "input"))
    )
    (net (code "8") (name "unconnected-(LED2-PadDOUT)") (class "Default")
      (node (ref "LED2") (pin "DOUT") (pinfunction "DOUT_DOUT") (pintype "output"))
    )
    (net (code "9") (name "unconnected-(LED3-PadDIN)") (class "Default")
      (node (ref "LED3") (pin "DIN") (pinfunction "DIN_DIN") (pintype "input"))
    )
    (net (code "10") (name "unconnected-(LED3-PadDOUT)") (class "Default")
      (node (ref "LED3") (pin "DOUT") (pinfunction "DOUT_DOUT") (pintype "output"))
    )
    (net (code "11") (name "unconnected-(LED4-PadDIN)") (class "Default")
      (node (ref "LED4") (pin "DIN") (pinfunction "DIN_DIN") (pintype "input"))
    )
    (net (code "12") (name "unconnected-(LED4-PadDOUT)") (class "Default")
      (node (ref "LED4") (pin "DOUT") (pinfunction "DOUT_DOUT") (pintype "output"))
    )
    (net (code "13") (name "unconnected-(LED5-PadDIN)") (class "Default")
      (node (ref "LED5") (pin "DIN") (pinfunction "DIN_DIN") (pintype "input"))
    )
    (net (code "14") (name "unconnected-(LED5-PadDOUT)") (class "Default")
      (node (ref "LED5") (pin "DOUT") (pinfunction "DOUT_DOUT") (pintype "output"))
    )
    (net (code "15") (name "unconnected-(LED6-PadDIN)") (class "Default")
      (node (ref "LED6") (pin "DIN") (pinfunction "DIN_DIN") (pintype "input"))
    )
    (net (code "16") (name "unconnected-(LED6-PadDOUT)") (class "Default")
      (node (ref "LED6") (pin "DOUT") (pinfunction "DOUT_DOUT") (pintype "output"))
    )
    (net (code "17") (name "unconnected-(LED7-PadDIN)") (class "Default")
      (node (ref "LED7") (pin "DIN") (pinfunction "DIN_DIN") (pintype "input"))
    )
    (net (code "18") (name "unconnected-(LED7-PadDOUT)") (class "Default")
      (node (ref "LED7") (pin "DOUT") (pinfunction "DOUT_DOUT") (pintype "output"))
    )
    (net (code "19") (name "unconnected-(LED8-PadDIN)") (class "Default")
      (node (ref "LED8") (pin "DIN") (pinfunction "DIN_DIN") (pintype "input"))
    )
    (net (code "20") (name "unconnected-(LED8-PadDOUT)") (class "Default")
      (node (ref "LED8") (pin "DOUT") (pinfunction "DOUT_DOUT") (pintype "output"))
    )
    (net (code "21") (name "unconnected-(LED9-PadDIN)") (class "Default")
      (node (ref "LED9") (pin "DIN") (pinfunction "DIN_DIN") (pintype "input"))
    )
    (net (code "22") (name "unconnected-(LED9-PadDOUT)") (class "Default")
      (node (ref "LED9") (pin "DOUT") (pinfunction "DOUT_DOUT") (pintype "output"))
    )
    (net (code "23") (name "unconnected-(LED10-PadDIN)") (class "Default")
      (node (ref "LED10") (pin "DIN") (pinfunction "DIN_DIN") (pintype "input"))
    )
    (net (code "24") (name "unconnected-(LED10-PadDOUT)") (class "Default")
      (node (ref "LED10") (pin "DOUT") (pinfunction "DOUT_DOUT") (pintype "output"))
    )
    (net (code "25") (name "unconnected-(LED11-PadDIN)") (class "Default")
      (node (ref "LED11") (pin "DIN") (pinfunction "DIN_DIN") (pintype "input"))
    )
    (net (code "26") (name "unconnected-(LED11-PadDOUT)") (class "Default")
      (node (ref "LED11") (pin "DOUT") (pinfunction "DOUT_DOUT") (pintype "output"))
    )
    (net (code "27") (name "unconnected-(LED12-PadDIN)") (class "Default")
      (node (ref "LED12") (pin "DIN") (pinfunction "DIN_DIN") (pintype "input"))
    )
    (net (code "28") (name "unconnected-(LED12-PadDOUT)") (class "Default")
      (node (ref "LED12") (pin "DOUT") (pinfunction "DOUT_DOUT") (pintype "output"))
    )
    (net (code "29") (name "unconnected-(LED13-PadDIN)") (class "Default")
      (node (ref "LED13") (pin "DIN") (pinfunction "DIN_DIN") (pintype "input"))
    )
    (net (code "30") (name "unconnected-(LED13-PadDOUT)") (class "Default")
      (node (ref "LED13") (pin "DOUT") (pinfunction "DOUT_DOUT") (pintype "output"))
    )
    (net (code "31") (name "unconnected-(LED14-PadDIN)") (class "Default")
      (node (ref "LED14") (pin "DIN") (pinfunction "DIN_DIN") (pintype "input"))
    )
    (net (code "32") (name "unconnected-(LED14-PadDOUT)") (class "Default")
      (node (ref "LED14") (pin "DOUT") (pinfunction "DOUT_DOUT") (pintype "output"))
    )
    (net (code "33") (name "unconnected-(LED15-PadDIN)") (class "Default")
      (node (ref "LED15") (pin "DIN") (pinfunction "DIN_DIN") (pintype "input"))
    )
    (net (code "34") (name "unconnected-(LED15-PadDOUT)") (class "Default")
      (node (ref "LED15") (pin "DOUT") (pinfunction "DOUT_DOUT") (pintype "output"))
    )
    (net (code "35") (name "unconnected-(LED16-PadDIN)") (class "Default")
      (node (ref "LED16") (pin "DIN") (pinfunction "DIN_DIN") (pintype "input"))
    )
    (net (code "36") (name "unconnected-(LED16-PadDOUT)") (class "Default")
      (node (ref "LED16") (pin "DOUT") (pinfunction "DOUT_DOUT") (pintype "output"))
    )
    (net (code "37") (name "unconnected-(LED17-PadDIN)") (class "Default")
      (node (ref "LED17") (pin "DIN") (pinfunction "DIN_DIN") (pintype "input"))
    )
    (net (code "38") (name "unconnected-(LED17-PadDOUT)") (class "Default")
      (node (ref "LED17") (pin "DOUT") (pinfunction "DOUT_DOUT") (pintype "output"))
    )
    (net (code "39") (name "unconnected-(LED18-PadDIN)") (class "Default")
      (node (ref "LED18") (pin "DIN") (pinfunction "DIN_DIN") (pintype "input"))
    )
    (net (code "40") (name "unconnected-(LED18-PadDOUT)") (class "Default")
      (node (ref "LED18") (pin "DOUT") (pinfunction "DOUT_DOUT") (pintype "output"))
    )
    (net (code "41") (name "unconnected-(LED19-PadDIN)") (class "Default")
      (node (ref "LED19") (pin "DIN") (pinfunction "DIN_DIN") (pintype "input"))
    )
    (net (code "42") (name "unconnected-(LED19-PadDOUT)") (class "Default")
      (node (ref "LED19") (pin "DOUT") (pinfunction "DOUT_DOUT") (pintype "output"))
    )
    (net (code "43") (name "unconnected-(LED20-PadDIN)") (class "Default")
      (node (ref "LED20") (pin "DIN") (pinfunction "DIN_DIN") (pintype "input"))
    )
    (net (code "44") (name "unconnected-(LED20-PadDOUT)") (class "Default")
      (node (ref "LED20") (pin "DOUT") (pinfunction "DOUT_DOUT") (pintype "output"))
    )
    (net (code "45") (name "unconnected-(LED21-PadDIN)") (class "Default")
      (node (ref "LED21") (pin "DIN") (pinfunction "DIN_DIN") (pintype "input"))
    )
    (net (code "46") (name "unconnected-(LED21-PadDOUT)") (class "Default")
      (node (ref "LED21") (pin "DOUT") (pinfunction "DOUT_DOUT") (pintype "output"))
    )
    (net (code "47") (name "unconnected-(LED22-PadDIN)") (class "Default")
      (node (ref "LED22") (pin "DIN") (pinfunction "DIN_DIN") (pintype "input"))
    )
    (net (code "48") (name "unconnected-(LED22-PadDOUT)") (class "Default")
      (node (ref "LED22") (pin "DOUT") (pinfunction "DOUT_DOUT") (pintype "output"))
    )
    (net (code "49") (name "unconnected-(LED23-PadDIN)") (class "Default")
      (node (ref "LED23") (pin "DIN") (pinfunction "DIN_DIN") (pintype "input"))
    )
    (net (code "50") (name "unconnected-(LED23-PadDOUT)") (class "Default")
      (node (ref "LED23") (pin "DOUT") (pinfunction "DOUT_DOUT") (pintype "output"))
    )
    (net (code "51") (name "unconnected-(LED24-PadDIN)") (class "Default")
      (node (ref "LED24") (pin "DIN") (pinfunction "DIN_DIN") (pintype "input"))
    )
    (net (code "52") (name "unconnected-(LED24-PadDOUT)") (class "Default")
      (node (ref "LED24") (pin "DOUT") (pinfunction "DOUT_DOUT") (pintype "output"))
    )
    (net (code "53") (name "unconnected-(LED25-PadDIN)") (class "Default")
      (node (ref "LED25") (pin "DIN") (pinfunction "DIN_DIN") (pintype "input"))
    )
    (net (code "54") (name "unconnected-(LED25-PadDOUT)") (class "Default")
      (node (ref "LED25") (pin "DOUT") (pinfunction "DOUT_DOUT") (pintype "output"))
    )
    (net (code "55") (name "unconnected-(LED26-PadDIN)") (class "Default")
      (node (ref "LED26") (pin "DIN") (pinfunction "DIN_DIN") (pintype "input"))
    )
    (net (code "56") (name "unconnected-(LED26-PadDOUT)") (class "Default")
      (node (ref "LED26") (pin "DOUT") (pinfunction "DOUT_DOUT") (pintype "output"))
    )
    (net (code "57") (name "unconnected-(LED27-PadDIN)") (class "Default")
      (node (ref "LED27") (pin "DIN") (pinfunction "DIN_DIN") (pintype "input"))
    )
    (net (code "58") (name "unconnected-(LED27-PadDOUT)") (class "Default")
      (node (ref "LED27") (pin "DOUT") (pinfunction "DOUT_DOUT") (pintype "output"))
    )
    (net (code "59") (name "unconnected-(LED28-PadDIN)") (class "Default")
      (node (ref "LED28") (pin "DIN") (pinfunction "DIN_DIN") (pintype "input"))
    )
    (net (code "60") (name "unconnected-(LED28-PadDOUT)") (class "Default")
      (node (ref "LED28") (pin "DOUT") (pinfunction "DOUT_DOUT") (pintype "output"))
    )
    (net (code "61") (name "unconnected-(LED29-PadDIN)") (class "Default")
      (node (ref "LED29") (pin "DIN") (pinfunction "DIN_DIN") (pintype "input"))
    )
    (net (code "62") (name "unconnected-(LED29-PadDOUT)") (class "Default")
      (node (ref "LED29") (pin "DOUT") (pinfunction "DOUT_DOUT") (pintype "output"))
    )
    (net (code "63") (name "unconnected-(LED30-PadDIN)") (class "Default")
      (node (ref "LED30") (pin "DIN") (pinfunction "DIN_DIN") (pintype "input"))
    )
    (net (code "64") (name "unconnected-(LED30-PadDOUT)") (class "Default")
      (node (ref "LED30") (pin "DOUT") (pinfunction "DOUT_DOUT") (pintype "output"))
    )
    (net (code "65") (name "unconnected-(LED31-PadDIN)") (class "Default")
      (node (ref "LED31") (pin "DIN") (pinfunction "DIN_DIN") (pintype "input"))
    )
    (net (code "66") (name "unconnected-(LED31-PadDOUT)") (class "Default")
      (node (ref "LED31") (pin "DOUT") (pinfunction "DOUT_DOUT") (pintype "output"))
    )
    (net (code "67") (name "unconnected-(LED32-PadDIN)") (class "Default")
      (node (ref "LED32") (pin "DIN") (pinfunction "DIN_DIN") (pintype "input"))
    )
    (net (code "68") (name "unconnected-(LED32-PadDOUT)") (class "Default")
      (node (ref "LED32") (pin "DOUT") (pinfunction "DOUT_DOUT") (pintype "output"))
    )
    (net (code "69") (name "unconnected-(LED33-PadDIN)") (class "Default")
      (node (ref "LED33") (pin "DIN") (pinfunction "DIN_DIN") (pintype "input"))
    )
    (net (code "70") (name "unconnected-(LED33-PadDOUT)") (class "Default")
      (node (ref "LED33") (pin "DOUT") (pinfunction "DOUT_DOUT") (pintype "output"))
    )
    (net (code "71") (name "unconnected-(LED34-PadDIN)") (class "Default")
      (node (ref "LED34") (pin "DIN") (pinfunction "DIN_DIN") (pintype "input"))
    )
    (net (code "72") (name "unconnected-(LED34-PadDOUT)") (class "Default")
      (node (ref "LED34") (pin "DOUT") (pinfunction "DOUT_DOUT") (pintype "output"))
    )
    (net (code "73") (name "unconnected-(LED35-PadDIN)") (class "Default")
      (node (ref "LED35") (pin "DIN") (pinfunction "DIN_DIN") (pintype "input"))
    )
    (net (code "74") (name "unconnected-(LED35-PadDOUT)") (class "Default")
      (node (ref "LED35") (pin "DOUT") (pinfunction "DOUT_DOUT") (pintype "output"))
    )
    (net (code "75") (name "unconnected-(LED36-PadDIN)") (class "Default")
      (node (ref "LED36") (pin "DIN") (pinfunction "DIN_DIN") (pintype "input"))
    )
    (net (code "76") (name "unconnected-(LED36-PadDOUT)") (class "Default")
      (node (ref "LED36") (pin "DOUT") (pinfunction "DOUT_DOUT") (pintype "output"))
    )
    (net (code "77") (name "unconnected-(LED37-PadDIN)") (class "Default")
      (node (ref "LED37") (pin "DIN") (pinfunction "DIN_DIN") (pintype "input"))
    )
    (net (code "78") (name "unconnected-(LED37-PadDOUT)") (class "Default")
      (node (ref "LED37") (pin "DOUT") (pinfunction "DOUT_DOUT") (pintype "output"))
    )
    (net (code "79") (name "unconnected-(LED38-PadDIN)") (class "Default")
      (node (ref "LED38") (pin "DIN") (pinfunction "DIN_DIN") (pintype "input"))
    )
    (net (code "80") (name "unconnected-(LED38-PadDOUT)") (class "Default")
      (node (ref "LED38") (pin "DOUT") (pinfunction "DOUT_DOUT") (pintype "output"))
    )
    (net (code "81") (name "unconnected-(LED39-PadDIN)") (class "Default")
      (node (ref "LED39") (pin "DIN") (pinfunction "DIN_DIN") (pintype "input"))
    )
    (net (code "82") (name "unconnected-(LED39-PadDOUT)") (class "Default")
      (node (ref "LED39") (pin "DOUT") (pinfunction "DOUT_DOUT") (pintype "output"))
    )
    (net (code "83") (name "unconnected-(LED40-PadDIN)") (class "Default")
      (node (ref "LED40") (pin "DIN") (pinfunction "DIN_DIN") (pintype "input"))
    )
    (net (code "84") (name "unconnected-(LED40-PadDOUT)") (class "Default")
      (node (ref "LED40") (pin "DOUT") (pinfunction "DOUT_DOUT") (pintype "output"))
    )
    (net (code "85") (name "unconnected-(LED41-PadDIN)") (class "Default")
      (node (ref "LED41") (pin "DIN") (pinfunction "DIN_DIN") (pintype "input"))
    )
    (net (code "86") (name "unconnected-(LED41-PadDOUT)") (class "Default")
      (node (ref "LED41") (pin "DOUT") (pinfunction "DOUT_DOUT") (pintype "output"))
    )
    (net (code "87") (name "unconnected-(LED42-PadDIN)") (class "Default")
      (node (ref "LED42") (pin "DIN") (pinfunction "DIN_DIN") (pintype "input"))
    )
    (net (code "88") (name "unconnected-(LED42-PadDOUT)") (class "Default")
      (node (ref "LED42") (pin "DOUT") (pinfunction "DOUT_DOUT") (pintype "output"))
    )
    (net (code "89") (name "unconnected-(LED43-PadDIN)") (class "Default")
      (node (ref "LED43") (pin "DIN") (pinfunction "DIN_DIN") (pintype "input"))
    )
    (net (code "90") (name "unconnected-(LED43-PadDOUT)") (class "Default")
      (node (ref "LED43") (pin "DOUT") (pinfunction "DOUT_DOUT") (pintype "output"))
    )
    (net (code "91") (name "unconnected-(LED44-PadDIN)") (class "Default")
      (node (ref "LED44") (pin "DIN") (pinfunction "DIN_DIN") (pintype "input"))
    )
    (net (code "92") (name "unconnected-(LED44-PadDOUT)") (class "Default")
      (node (ref "LED44") (pin "DOUT") (pinfunction "DOUT_DOUT") (pintype "output"))
    )
    (net (code "93") (name "unconnected-(LED45-PadDIN)") (class "Default")
      (node (ref "LED45") (pin "DIN") (pinfunction "DIN_DIN") (pintype "input"))
    )
    (net (code "94") (name "unconnected-(LED45-PadDOUT)") (class "Default")
      (node (ref "LED45") (pin "DOUT") (pinfunction "DOUT_DOUT") (pintype "output"))
    )
    (net (code "95") (name "unconnected-(LED46-PadDIN)") (class "Default")
      (node (ref "LED46") (pin "DIN") (pinfunction "DIN_DIN") (pintype "input"))
    )
    (net (code "96") (name "unconnected-(LED46-PadDOUT)") (class "Default")
      (node (ref "LED46") (pin "DOUT") (pinfunction "DOUT_DOUT") (pintype "output"))
    )
    (net (code "97") (name "unconnected-(LED47-PadDIN)") (class "Default")
      (node (ref "LED47") (pin "DIN") (pinfunction "DIN_DIN") (pintype "input"))
    )
    (net (code "98") (name "unconnected-(LED47-PadDOUT)") (class "Default")
      (node (ref "LED47") (pin "DOUT") (pinfunction "DOUT_DOUT") (pintype "output"))
    )
    (net (code "99") (name "unconnected-(LED48-PadDIN)") (class "Default")
      (node (ref "LED48") (pin "DIN") (pinfunction "DIN_DIN") (pintype "input"))
    )
    (net (code "100") (name "unconnected-(LED48-PadDOUT)") (class "Default")
      (node (ref "LED48") (pin "DOUT") (pinfunction "DOUT_DOUT") (pintype "output"))
    )
    (net (code "101") (name "unconnected-(LED49-PadDIN)") (class "Default")
      (node (ref "LED49") (pin "DIN") (pinfunction "DIN_DIN") (pintype "input"))
    )
    (net (code "102") (name "unconnected-(LED49-PadDOUT)") (class "Default")
      (node (ref "LED49") (pin "DOUT") (pinfunction "DOUT_DOUT") (pintype "output"))
    )
    (net (code "103") (name "unconnected-(LED50-PadDIN)") (class "Default")
      (node (ref "LED50") (pin "DIN") (pinfunction "DIN_DIN") (pintype "input"))
    )
    (net (code "104") (name "unconnected-(LED50-PadDOUT)") (class "Default")
      (node (ref "LED50") (pin "DOUT") (pinfunction "DOUT_DOUT") (pintype "output"))
    )
    (net (code "105") (name "unconnected-(LED51-PadDIN)") (class "Default")
      (node (ref "LED51") (pin "DIN") (pinfunction "DIN_DIN") (pintype "input"))
    )
    (net (code "106") (name "unconnected-(LED51-PadDOUT)") (class "Default")
      (node (ref "LED51") (pin "DOUT") (pinfunction "DOUT_DOUT") (pintype "output"))
    )
    (net (code "107") (name "unconnected-(LED52-PadDIN)") (class "Default")
      (node (ref "LED52") (pin "DIN") (pinfunction "DIN_DIN") (pintype "input"))
    )
    (net (code "108") (name "unconnected-(LED52-PadDOUT)") (class "Default")
      (node (ref "LED52") (pin "DOUT") (pinfunction "DOUT_DOUT") (pintype "output"))
    )
    (net (code "109") (name "unconnected-(LED53-PadDIN)") (class "Default")
      (node (ref "LED53") (pin "DIN") (pinfunction "DIN_DIN") (pintype "input"))
    )
    (net (code "110") (name "unconnected-(LED53-PadDOUT)") (class "Default")
      (node (ref "LED53") (pin "DOUT") (pinfunction "DOUT_DOUT") (pintype "output"))
    )
    (net (code "111") (name "unconnected-(LED54-PadDIN)") (class "Default")
      (node (ref "LED54") (pin "DIN") (pinfunction "DIN_DIN") (pintype "input"))
    )
    (net (code "112") (name "unconnected-(LED54-PadDOUT)") (class "Default")
      (node (ref "LED54") (pin "DOUT") (pinfunction "DOUT_DOUT") (pintype "output"))
    )
    (net (code "113") (name "unconnected-(LED55-PadDIN)") (class "Default")
      (node (ref "LED55") (pin "DIN") (pinfunction "DIN_DIN") (pintype "input"))
    )
    (net (code "114") (name "unconnected-(LED55-PadDOUT)") (class "Default")
      (node (ref "LED55") (pin "DOUT") (pinfunction "DOUT_DOUT") (pintype "output"))
    )
    (net (code "115") (name "unconnected-(LED56-PadDIN)") (class "Default")
      (node (ref "LED56") (pin "DIN") (pinfunction "DIN_DIN") (pintype "input"))
    )
    (net (code "116") (name "unconnected-(LED56-PadDOUT)") (class "Default")
      (node (ref "LED56") (pin "DOUT") (pinfunction "DOUT_DOUT") (pintype "output"))
    )
    (net (code "117") (name "unconnected-(LED57-PadDIN)") (class "Default")
      (node (ref "LED57") (pin "DIN") (pinfunction "DIN_DIN") (pintype "input"))
    )
    (net (code "118") (name "unconnected-(LED57-PadDOUT)") (class "Default")
      (node (ref "LED57") (pin "DOUT") (pinfunction "DOUT_DOUT") (pintype "output"))
    )
    (net (code "119") (name "unconnected-(LED58-PadDIN)") (class "Default")
      (node (ref "LED58") (pin "DIN") (pinfunction "DIN_DIN") (pintype "input"))
    )
    (net (code "120") (name "unconnected-(LED58-PadDOUT)") (class "Default")
      (node (ref "LED58") (pin "DOUT") (pinfunction "DOUT_DOUT") (pintype "output"))
    )
    (net (code "121") (name "unconnected-(LED59-PadDIN)") (class "Default")
      (node (ref "LED59") (pin "DIN") (pinfunction "DIN_DIN") (pintype "input"))
    )
    (net (code "122") (name "unconnected-(LED59-PadDOUT)") (class "Default")
      (node (ref "LED59") (pin "DOUT") (pinfunction "DOUT_DOUT") (pintype "output"))
    )
    (net (code "123") (name "unconnected-(LED60-PadDIN)") (class "Default")
      (node (ref "LED60") (pin "DIN") (pinfunction "DIN_DIN") (pintype "input"))
    )
    (net (code "124") (name "unconnected-(LED60-PadDOUT)") (class "Default")
      (node (ref "LED60") (pin "DOUT") (pinfunction "DOUT_DOUT") (pintype "output"))
    )
    (net (code "125") (name "unconnected-(LED61-A-Pad10)") (class "Default")
      (node (ref "LED61") (pin "10") (pinfunction "A_10") (pintype "passive"))
    )
    (net (code "126") (name "unconnected-(LED61-B-Pad9)") (class "Default")
      (node (ref "LED61") (pin "9") (pinfunction "B_9") (pintype "passive"))
    )
    (net (code "127") (name "unconnected-(LED61-C-Pad8)") (class "Default")
      (node (ref "LED61") (pin "8") (pinfunction "C_8") (pintype "passive"))
    )
    (net (code "128") (name "unconnected-(LED61-CA2-Pad6)") (class "Default")
      (node (ref "LED61") (pin "6") (pinfunction "CA2_6") (pintype "passive"))
    )
    (net (code "129") (name "unconnected-(LED61-D-Pad5)") (class "Default")
      (node (ref "LED61") (pin "5") (pinfunction "D_5") (pintype "passive"))
    )
    (net (code "130") (name "unconnected-(LED61-DP-Pad7)") (class "Default")
      (node (ref "LED61") (pin "7") (pinfunction "DP_7") (pintype "passive"))
    )
    (net (code "131") (name "unconnected-(LED61-E-Pad1)") (class "Default")
      (node (ref "LED61") (pin "1") (pinfunction "E_1") (pintype "passive"))
    )
    (net (code "132") (name "unconnected-(LED61-F-Pad2)") (class "Default")
      (node (ref "LED61") (pin "2") (pinfunction "F_2") (pintype "passive"))
    )
    (net (code "133") (name "unconnected-(LED61-G-Pad3)") (class "Default")
      (node (ref "LED61") (pin "3") (pinfunction "G_3") (pintype "passive"))
    )
    (net (code "134") (name "unconnected-(LED62-A-Pad10)") (class "Default")
      (node (ref "LED62") (pin "10") (pinfunction "A_10") (pintype "passive"))
    )
    (net (code "135") (name "unconnected-(LED62-B-Pad9)") (class "Default")
      (node (ref "LED62") (pin "9") (pinfunction "B_9") (pintype "passive"))
    )
    (net (code "136") (name "unconnected-(LED62-C-Pad8)") (class "Default")
      (node (ref "LED62") (pin "8") (pinfunction "C_8") (pintype "passive"))
    )
    (net (code "137") (name "unconnected-(LED62-CA2-Pad6)") (class "Default")
      (node (ref "LED62") (pin "6") (pinfunction "CA2_6") (pintype "passive"))
    )
    (net (code "138") (name "unconnected-(LED62-D-Pad5)") (class "Default")
      (node (ref "LED62") (pin "5") (pinfunction "D_5") (pintype "passive"))
    )
    (net (code "139") (name "unconnected-(LED62-DP-Pad7)") (class "Default")
      (node (ref "LED62") (pin "7") (pinfunction "DP_7") (pintype "passive"))
    )
    (net (code "140") (name "unconnected-(LED62-E-Pad1)") (class "Default")
      (node (ref "LED62") (pin "1") (pinfunction "E_1") (pintype "passive"))
    )
    (net (code "141") (name "unconnected-(LED62-F-Pad2)") (class "Default")
      (node (ref "LED62") (pin "2") (pinfunction "F_2") (pintype "passive"))
    )
    (net (code "142") (name "unconnected-(LED62-G-Pad3)") (class "Default")
      (node (ref "LED62") (pin "3") (pinfunction "G_3") (pintype "passive"))
    )
    (net (code "143") (name "unconnected-(SV1-Pad4)") (class "Default")
      (node (ref "SV1") (pin "4") (pinfunction "4_4") (pintype "passive"))
    )
    (net (code "144") (name "unconnected-(SV1-Pad5)") (class "Default")
      (node (ref "SV1") (pin "5") (pinfunction "5_5") (pintype "passive"))
    )
    (net (code "145") (name "unconnected-(SV1-Pad6)") (class "Default")
      (node (ref "SV1") (pin "6") (pinfunction "6_6") (pintype "passive"))
    )
    (net (code "146") (name "unconnected-(SV1-Pad7)") (class "Default")
      (node (ref "SV1") (pin "7") (pinfunction "7_7") (pintype "passive"))
    )
    (net (code "147") (name "unconnected-(SV1-Pad8)") (class "Default")
      (node (ref "SV1") (pin "8") (pinfunction "8_8") (pintype "passive"))
    )
  )
)
